# derploadxp.net
KiCad netlist of a schematic drawn in EAGLE
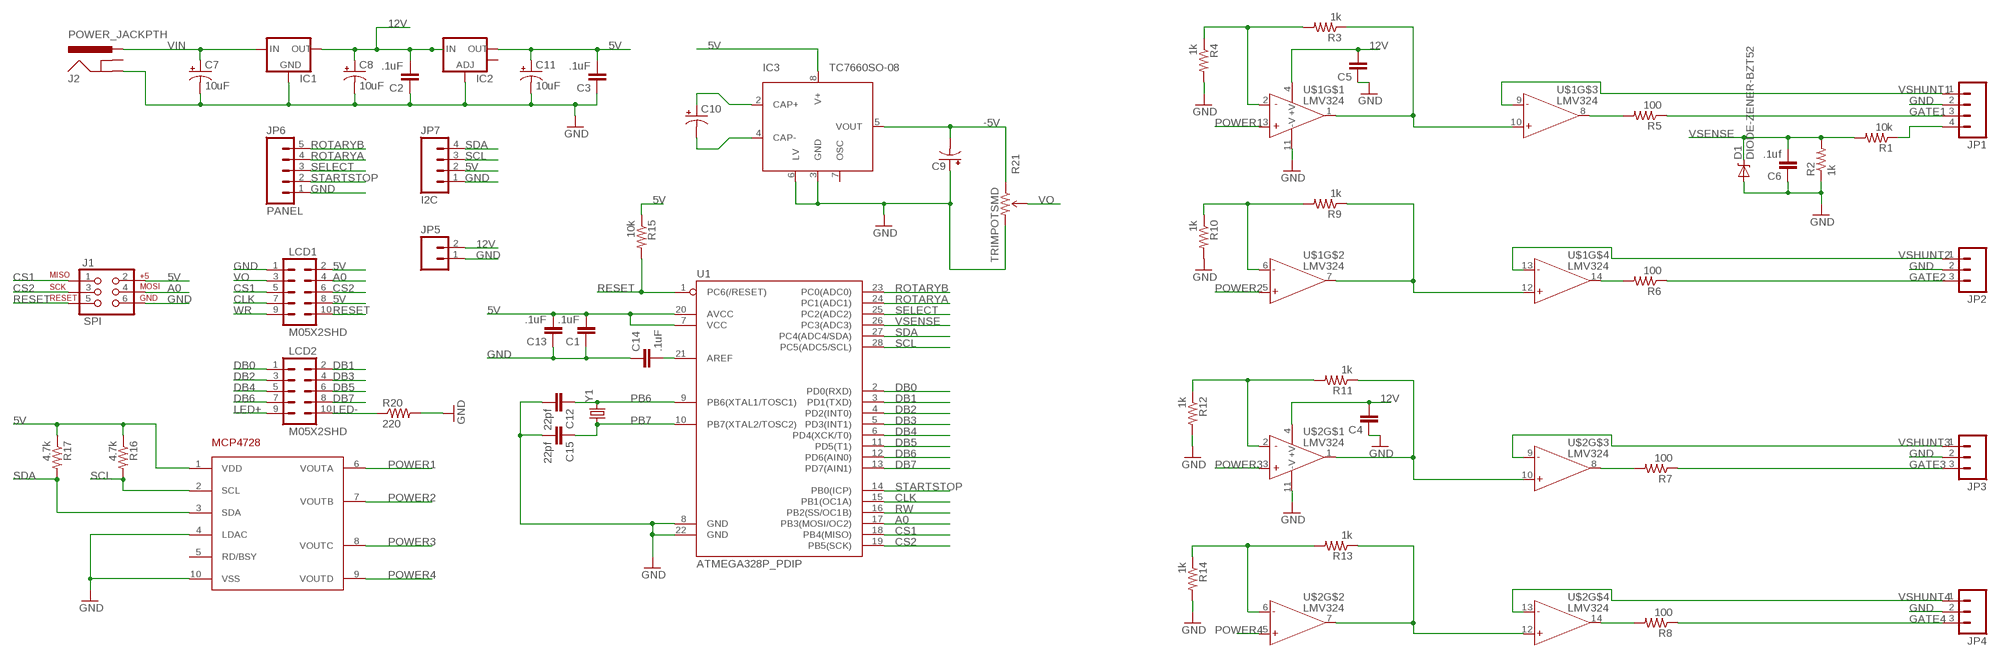
[diagram p0: schematic, sheet 1]

(export (version "E")
  (design (tool "Eeschema 10.0.6"))
  (components
    (comp (ref "C1")
      (value ".1uF")
      (footprint "eagle-import:0805")
      (libsource (lib "eagle-import") (part "CAP0805"))
    )
    (comp (ref "C2")
      (value ".1uF")
      (footprint "eagle-import:0805")
      (libsource (lib "eagle-import") (part "CAP0805"))
    )
    (comp (ref "C3")
      (value ".1uF")
      (footprint "eagle-import:0805")
      (libsource (lib "eagle-import") (part "CAP0805"))
    )
    (comp (ref "C4")
      (value "CAP0805")
      (footprint "eagle-import:0805")
      (libsource (lib "eagle-import") (part "CAP0805"))
    )
    (comp (ref "C5")
      (value "CAP0805")
      (footprint "eagle-import:0805")
      (libsource (lib "eagle-import") (part "CAP0805"))
    )
    (comp (ref "C6")
      (value ".1uf")
      (footprint "eagle-import:0805")
      (libsource (lib "eagle-import") (part "CAP0805"))
    )
    (comp (ref "C7")
      (value "10uF")
      (footprint "eagle-import:PANASONIC_C")
      (libsource (lib "eagle-import") (part "CAP_POLC"))
    )
    (comp (ref "C8")
      (value "10uF")
      (footprint "eagle-import:PANASONIC_C")
      (libsource (lib "eagle-import") (part "CAP_POLC"))
    )
    (comp (ref "C9")
      (value "CAP_POLC")
      (footprint "eagle-import:PANASONIC_C")
      (libsource (lib "eagle-import") (part "CAP_POLC"))
    )
    (comp (ref "C10")
      (value "CAP_POLC")
      (footprint "eagle-import:PANASONIC_C")
      (libsource (lib "eagle-import") (part "CAP_POLC"))
    )
    (comp (ref "C11")
      (value "10uF")
      (footprint "eagle-import:PANASONIC_C")
      (libsource (lib "eagle-import") (part "CAP_POLC"))
    )
    (comp (ref "C12")
      (value "22pf")
      (footprint "eagle-import:0805")
      (libsource (lib "eagle-import") (part "CAP0805"))
    )
    (comp (ref "C13")
      (value ".1uF")
      (footprint "eagle-import:0805")
      (libsource (lib "eagle-import") (part "CAP0805"))
    )
    (comp (ref "C14")
      (value ".1uF")
      (footprint "eagle-import:0805")
      (libsource (lib "eagle-import") (part "CAP0805"))
    )
    (comp (ref "C15")
      (value "22pf")
      (footprint "eagle-import:0805")
      (libsource (lib "eagle-import") (part "CAP0805"))
    )
    (comp (ref "D1")
      (value "DIODE-ZENER-BZT52")
      (footprint "eagle-import:SOD-323")
      (libsource (lib "eagle-import") (part "DIODE-ZENER-BZT52"))
    )
    (comp (ref "IC1")
      (value "V_REG_78XXSINK")
      (footprint "eagle-import:TO220-IGO")
      (libsource (lib "eagle-import") (part "V_REG_78XXSINK"))
    )
    (comp (ref "IC2")
      (value "V_REG_LM1117SOT223")
      (footprint "eagle-import:SOT223")
      (libsource (lib "eagle-import") (part "V_REG_LM1117SOT223"))
    )
    (comp (ref "IC3")
      (value "TC7660SO-08")
      (footprint "eagle-import:SO-08")
      (libsource (lib "eagle-import") (part "TC7660SO-08"))
    )
    (comp (ref "J1")
      (value "SPI")
      (footprint "eagle-import:2X3-NS")
      (libsource (lib "eagle-import") (part "AVR_SPI_PRG_6NS"))
    )
    (comp (ref "J2")
      (value "POWER_JACKPTH")
      (footprint "eagle-import:POWER_JACK_PTH")
      (libsource (lib "eagle-import") (part "POWER_JACKPTH"))
    )
    (comp (ref "JP1")
      (value "M04LOCK")
      (footprint "eagle-import:1X04_LOCK")
      (libsource (lib "eagle-import") (part "M04LOCK"))
    )
    (comp (ref "JP2")
      (value "M03LOCK")
      (footprint "eagle-import:1X03_LOCK")
      (libsource (lib "eagle-import") (part "M03LOCK"))
    )
    (comp (ref "JP3")
      (value "M03LOCK")
      (footprint "eagle-import:1X03_LOCK")
      (libsource (lib "eagle-import") (part "M03LOCK"))
    )
    (comp (ref "JP4")
      (value "M03LOCK")
      (footprint "eagle-import:1X03_LOCK")
      (libsource (lib "eagle-import") (part "M03LOCK"))
    )
    (comp (ref "JP5")
      (value "M02LOCK")
      (footprint "eagle-import:1X02_LOCK")
      (libsource (lib "eagle-import") (part "M02LOCK"))
    )
    (comp (ref "JP6")
      (value "PANEL")
      (footprint "eagle-import:1X05_LOCK")
      (libsource (lib "eagle-import") (part "M05LOCK"))
    )
    (comp (ref "JP7")
      (value "I2C")
      (footprint "eagle-import:1X04_LOCK")
      (libsource (lib "eagle-import") (part "M04LOCK"))
    )
    (comp (ref "LCD1")
      (value "M05X2SHD")
      (footprint "eagle-import:2X5-SHROUDED")
      (libsource (lib "eagle-import") (part "M05X2SHD"))
    )
    (comp (ref "LCD2")
      (value "M05X2SHD")
      (footprint "eagle-import:2X5-SHROUDED")
      (libsource (lib "eagle-import") (part "M05X2SHD"))
    )
    (comp (ref "R1")
      (value "10k")
      (footprint "eagle-import:0805")
      (libsource (lib "eagle-import") (part "RESISTOR0805-RES"))
    )
    (comp (ref "R2")
      (value "1k")
      (footprint "eagle-import:0805")
      (libsource (lib "eagle-import") (part "RESISTOR0805-RES"))
    )
    (comp (ref "R3")
      (value "1k")
      (footprint "eagle-import:0805")
      (libsource (lib "eagle-import") (part "RESISTOR0805-RES"))
    )
    (comp (ref "R4")
      (value "1k")
      (footprint "eagle-import:0805")
      (libsource (lib "eagle-import") (part "RESISTOR0805-RES"))
    )
    (comp (ref "R5")
      (value "100")
      (footprint "eagle-import:0805")
      (libsource (lib "eagle-import") (part "RESISTOR0805-RES"))
    )
    (comp (ref "R6")
      (value "100")
      (footprint "eagle-import:0805")
      (libsource (lib "eagle-import") (part "RESISTOR0805-RES"))
    )
    (comp (ref "R7")
      (value "100")
      (footprint "eagle-import:0805")
      (libsource (lib "eagle-import") (part "RESISTOR0805-RES"))
    )
    (comp (ref "R8")
      (value "100")
      (footprint "eagle-import:0805")
      (libsource (lib "eagle-import") (part "RESISTOR0805-RES"))
    )
    (comp (ref "R9")
      (value "1k")
      (footprint "eagle-import:0805")
      (libsource (lib "eagle-import") (part "RESISTOR0805-RES"))
    )
    (comp (ref "R10")
      (value "1k")
      (footprint "eagle-import:0805")
      (libsource (lib "eagle-import") (part "RESISTOR0805-RES"))
    )
    (comp (ref "R11")
      (value "1k")
      (footprint "eagle-import:0805")
      (libsource (lib "eagle-import") (part "RESISTOR0805-RES"))
    )
    (comp (ref "R12")
      (value "1k")
      (footprint "eagle-import:0805")
      (libsource (lib "eagle-import") (part "RESISTOR0805-RES"))
    )
    (comp (ref "R13")
      (value "1k")
      (footprint "eagle-import:0805")
      (libsource (lib "eagle-import") (part "RESISTOR0805-RES"))
    )
    (comp (ref "R14")
      (value "1k")
      (footprint "eagle-import:0805")
      (libsource (lib "eagle-import") (part "RESISTOR0805-RES"))
    )
    (comp (ref "R15")
      (value "10k")
      (footprint "eagle-import:0805")
      (libsource (lib "eagle-import") (part "RESISTOR0805-RES"))
    )
    (comp (ref "R16")
      (value "4.7k")
      (footprint "eagle-import:0805")
      (libsource (lib "eagle-import") (part "RESISTOR0805-RES"))
    )
    (comp (ref "R17")
      (value "4.7k")
      (footprint "eagle-import:0805")
      (libsource (lib "eagle-import") (part "RESISTOR0805-RES"))
    )
    (comp (ref "R20")
      (value "220")
      (footprint "eagle-import:0805")
      (libsource (lib "eagle-import") (part "RESISTOR0805-RES"))
    )
    (comp (ref "R21")
      (value "TRIMPOTSMD")
      (footprint "eagle-import:TRIMPOT-3MM")
      (libsource (lib "eagle-import") (part "TRIMPOTSMD"))
    )
    (comp (ref "U$1")
      (value "LMV324")
      (footprint "eagle-import:SO014")
      (libsource (lib "eagle-import") (part "LMV324"))
    )
    (comp (ref "U$2")
      (value "LMV324")
      (footprint "eagle-import:SO014")
      (libsource (lib "eagle-import") (part "LMV324"))
    )
    (comp (ref "U$4")
      (value "MCP4728")
      (footprint "eagle-import:MSOP10")
      (libsource (lib "eagle-import") (part "MCP4728"))
    )
    (comp (ref "U1")
      (value "ATMEGA328P_PDIP")
      (footprint "eagle-import:DIL28-3")
      (libsource (lib "eagle-import") (part "ATMEGA328P_PDIP"))
    )
    (comp (ref "Y1")
      (value "CRYSTALSMD")
      (footprint "eagle-import:HC49UP")
      (libsource (lib "eagle-import") (part "CRYSTALSMD"))
    )
  )
  (nets
    (net (code "1") (name "/-5V") (class "Default")
      (node (ref "C9") (pin "-") (pinfunction "-_-") (pintype "passive"))
      (node (ref "IC3") (pin "5") (pinfunction "VOUT_5") (pintype "bidirectional"))
      (node (ref "R21") (pin "1") (pinfunction "CCW_1") (pintype "passive"))
    )
    (net (code "2") (name "/5V") (class "Default")
      (node (ref "C1") (pin "2") (pinfunction "2_2") (pintype "passive"))
      (node (ref "C11") (pin "+") (pinfunction "+_+") (pintype "passive"))
      (node (ref "C13") (pin "2") (pinfunction "2_2") (pintype "passive"))
      (node (ref "C3") (pin "2") (pinfunction "2_2") (pintype "passive"))
      (node (ref "IC2") (pin "2") (pinfunction "OUT_2") (pintype "output"))
      (node (ref "IC3") (pin "8") (pinfunction "V+_8") (pintype "bidirectional"))
      (node (ref "J1") (pin "2") (pinfunction "2_2") (pintype "passive"))
      (node (ref "JP7") (pin "2") (pinfunction "2_2") (pintype "passive"))
      (node (ref "LCD1") (pin "2") (pinfunction "2_2") (pintype "passive"))
      (node (ref "LCD1") (pin "8") (pinfunction "8_8") (pintype "passive"))
      (node (ref "R15") (pin "1") (pinfunction "1_1") (pintype "passive"))
      (node (ref "R16") (pin "1") (pinfunction "1_1") (pintype "passive"))
      (node (ref "R17") (pin "1") (pinfunction "1_1") (pintype "passive"))
      (node (ref "U$4") (pin "1") (pinfunction "VDD_1") (pintype "bidirectional"))
      (node (ref "U1") (pin "20") (pinfunction "AVCC_20") (pintype "bidirectional"))
      (node (ref "U1") (pin "7") (pinfunction "VCC_7") (pintype "bidirectional"))
    )
    (net (code "3") (name "/12V") (class "Default")
      (node (ref "C2") (pin "2") (pinfunction "2_2") (pintype "passive"))
      (node (ref "C4") (pin "2") (pinfunction "2_2") (pintype "passive"))
      (node (ref "C5") (pin "2") (pinfunction "2_2") (pintype "passive"))
      (node (ref "C8") (pin "+") (pinfunction "+_+") (pintype "passive"))
      (node (ref "IC1") (pin "OUT") (pinfunction "OUT_OUT") (pintype "output"))
      (node (ref "IC2") (pin "3") (pinfunction "IN_3") (pintype "input"))
      (node (ref "JP5") (pin "2") (pinfunction "2_2") (pintype "passive"))
      (node (ref "U$1") (pin "4") (pinfunction "+V_4") (pintype "power_in"))
      (node (ref "U$2") (pin "4") (pinfunction "+V_4") (pintype "power_in"))
    )
    (net (code "4") (name "/A0") (class "Default")
      (node (ref "J1") (pin "4") (pinfunction "4_4") (pintype "passive"))
      (node (ref "LCD1") (pin "4") (pinfunction "4_4") (pintype "passive"))
      (node (ref "U1") (pin "17") (pinfunction "PB3(MOSI/OC2)_17") (pintype "bidirectional"))
    )
    (net (code "5") (name "/CLK") (class "Default")
      (node (ref "LCD1") (pin "7") (pinfunction "7_7") (pintype "passive"))
      (node (ref "U1") (pin "15") (pinfunction "PB1(OC1A)_15") (pintype "bidirectional"))
    )
    (net (code "6") (name "/CS1") (class "Default")
      (node (ref "J1") (pin "1") (pinfunction "1_1") (pintype "passive"))
      (node (ref "LCD1") (pin "5") (pinfunction "5_5") (pintype "passive"))
      (node (ref "U1") (pin "18") (pinfunction "PB4(MISO)_18") (pintype "bidirectional"))
    )
    (net (code "7") (name "/CS2") (class "Default")
      (node (ref "J1") (pin "3") (pinfunction "3_3") (pintype "passive"))
      (node (ref "LCD1") (pin "6") (pinfunction "6_6") (pintype "passive"))
      (node (ref "U1") (pin "19") (pinfunction "PB5(SCK)_19") (pintype "bidirectional"))
    )
    (net (code "8") (name "/DB0") (class "Default")
      (node (ref "LCD2") (pin "1") (pinfunction "1_1") (pintype "passive"))
      (node (ref "U1") (pin "2") (pinfunction "PD0(RXD)_2") (pintype "bidirectional"))
    )
    (net (code "9") (name "/DB1") (class "Default")
      (node (ref "LCD2") (pin "2") (pinfunction "2_2") (pintype "passive"))
      (node (ref "U1") (pin "3") (pinfunction "PD1(TXD)_3") (pintype "bidirectional"))
    )
    (net (code "10") (name "/DB2") (class "Default")
      (node (ref "LCD2") (pin "3") (pinfunction "3_3") (pintype "passive"))
      (node (ref "U1") (pin "4") (pinfunction "PD2(INT0)_4") (pintype "bidirectional"))
    )
    (net (code "11") (name "/DB3") (class "Default")
      (node (ref "LCD2") (pin "4") (pinfunction "4_4") (pintype "passive"))
      (node (ref "U1") (pin "5") (pinfunction "PD3(INT1)_5") (pintype "bidirectional"))
    )
    (net (code "12") (name "/DB4") (class "Default")
      (node (ref "LCD2") (pin "5") (pinfunction "5_5") (pintype "passive"))
      (node (ref "U1") (pin "6") (pinfunction "PD4(XCK/T0)_6") (pintype "bidirectional"))
    )
    (net (code "13") (name "/DB5") (class "Default")
      (node (ref "LCD2") (pin "6") (pinfunction "6_6") (pintype "passive"))
      (node (ref "U1") (pin "11") (pinfunction "PD5(T1)_11") (pintype "bidirectional"))
    )
    (net (code "14") (name "/DB6") (class "Default")
      (node (ref "LCD2") (pin "7") (pinfunction "7_7") (pintype "passive"))
      (node (ref "U1") (pin "12") (pinfunction "PD6(AIN0)_12") (pintype "bidirectional"))
    )
    (net (code "15") (name "/DB7") (class "Default")
      (node (ref "LCD2") (pin "8") (pinfunction "8_8") (pintype "passive"))
      (node (ref "U1") (pin "13") (pinfunction "PD7(AIN1)_13") (pintype "bidirectional"))
    )
    (net (code "16") (name "/GATE1") (class "Default")
      (node (ref "JP1") (pin "3") (pinfunction "3_3") (pintype "passive"))
      (node (ref "R5") (pin "1") (pinfunction "1_1") (pintype "passive"))
    )
    (net (code "17") (name "/GATE2") (class "Default")
      (node (ref "JP2") (pin "3") (pinfunction "3_3") (pintype "passive"))
      (node (ref "R6") (pin "1") (pinfunction "1_1") (pintype "passive"))
    )
    (net (code "18") (name "/GATE3") (class "Default")
      (node (ref "JP3") (pin "3") (pinfunction "3_3") (pintype "passive"))
      (node (ref "R7") (pin "1") (pinfunction "1_1") (pintype "passive"))
    )
    (net (code "19") (name "/GATE4") (class "Default")
      (node (ref "JP4") (pin "3") (pinfunction "3_3") (pintype "passive"))
      (node (ref "R8") (pin "1") (pinfunction "1_1") (pintype "passive"))
    )
    (net (code "20") (name "/LED+") (class "Default")
      (node (ref "LCD2") (pin "9") (pinfunction "9_9") (pintype "passive"))
    )
    (net (code "21") (name "/LED-") (class "Default")
      (node (ref "LCD2") (pin "10") (pinfunction "10_10") (pintype "passive"))
      (node (ref "R20") (pin "1") (pinfunction "1_1") (pintype "passive"))
    )
    (net (code "22") (name "/PB6") (class "Default")
      (node (ref "C12") (pin "1") (pinfunction "1_1") (pintype "passive"))
      (node (ref "U1") (pin "9") (pinfunction "PB6(XTAL1/TOSC1)_9") (pintype "bidirectional"))
      (node (ref "Y1") (pin "2") (pinfunction "2_2") (pintype "passive"))
    )
    (net (code "23") (name "/PB7") (class "Default")
      (node (ref "C15") (pin "1") (pinfunction "1_1") (pintype "passive"))
      (node (ref "U1") (pin "10") (pinfunction "PB7(XTAL2/TOSC2)_10") (pintype "bidirectional"))
      (node (ref "Y1") (pin "1") (pinfunction "1_1") (pintype "passive"))
    )
    (net (code "24") (name "/POWER1") (class "Default")
      (node (ref "U$1") (pin "3") (pinfunction "+IN_3") (pintype "input"))
      (node (ref "U$4") (pin "6") (pinfunction "VOUTA_6") (pintype "bidirectional"))
    )
    (net (code "25") (name "/POWER2") (class "Default")
      (node (ref "U$1") (pin "5") (pinfunction "+IN_5") (pintype "power_in"))
      (node (ref "U$4") (pin "7") (pinfunction "VOUTB_7") (pintype "bidirectional"))
    )
    (net (code "26") (name "/POWER3") (class "Default")
      (node (ref "U$2") (pin "3") (pinfunction "+IN_3") (pintype "input"))
      (node (ref "U$4") (pin "8") (pinfunction "VOUTC_8") (pintype "bidirectional"))
    )
    (net (code "27") (name "/POWER4") (class "Default")
      (node (ref "U$2") (pin "5") (pinfunction "+IN_5") (pintype "power_in"))
      (node (ref "U$4") (pin "9") (pinfunction "VOUTD_9") (pintype "bidirectional"))
    )
    (net (code "28") (name "/RESET") (class "Default")
      (node (ref "J1") (pin "5") (pinfunction "5_5") (pintype "passive"))
      (node (ref "LCD1") (pin "10") (pinfunction "10_10") (pintype "passive"))
      (node (ref "R15") (pin "2") (pinfunction "2_2") (pintype "passive"))
      (node (ref "U1") (pin "1") (pinfunction "PC6(/RESET)_1") (pintype "bidirectional"))
    )
    (net (code "29") (name "/ROTARYA") (class "Default")
      (node (ref "JP6") (pin "4") (pinfunction "4_4") (pintype "passive"))
      (node (ref "U1") (pin "24") (pinfunction "PC1(ADC1)_24") (pintype "bidirectional"))
    )
    (net (code "30") (name "/ROTARYB") (class "Default")
      (node (ref "JP6") (pin "5") (pinfunction "5_5") (pintype "passive"))
      (node (ref "U1") (pin "23") (pinfunction "PC0(ADC0)_23") (pintype "bidirectional"))
    )
    (net (code "31") (name "/RW") (class "Default")
      (node (ref "U1") (pin "16") (pinfunction "PB2(SS/OC1B)_16") (pintype "bidirectional"))
    )
    (net (code "32") (name "/SCL") (class "Default")
      (node (ref "JP7") (pin "3") (pinfunction "3_3") (pintype "passive"))
      (node (ref "R16") (pin "2") (pinfunction "2_2") (pintype "passive"))
      (node (ref "U$4") (pin "2") (pinfunction "SCL_2") (pintype "bidirectional"))
      (node (ref "U1") (pin "28") (pinfunction "PC5(ADC5/SCL)_28") (pintype "bidirectional"))
    )
    (net (code "33") (name "/SDA") (class "Default")
      (node (ref "JP7") (pin "4") (pinfunction "4_4") (pintype "passive"))
      (node (ref "R17") (pin "2") (pinfunction "2_2") (pintype "passive"))
      (node (ref "U$4") (pin "3") (pinfunction "SDA_3") (pintype "bidirectional"))
      (node (ref "U1") (pin "27") (pinfunction "PC4(ADC4/SDA)_27") (pintype "bidirectional"))
    )
    (net (code "34") (name "/SELECT") (class "Default")
      (node (ref "JP6") (pin "3") (pinfunction "3_3") (pintype "passive"))
      (node (ref "U1") (pin "25") (pinfunction "PC2(ADC2)_25") (pintype "bidirectional"))
    )
    (net (code "35") (name "/STARTSTOP") (class "Default")
      (node (ref "JP6") (pin "2") (pinfunction "2_2") (pintype "passive"))
      (node (ref "U1") (pin "14") (pinfunction "PB0(ICP)_14") (pintype "bidirectional"))
    )
    (net (code "36") (name "/VIN") (class "Default")
      (node (ref "C7") (pin "+") (pinfunction "+_+") (pintype "passive"))
      (node (ref "IC1") (pin "IN") (pinfunction "IN_IN") (pintype "input"))
      (node (ref "J2") (pin "PWR") (pinfunction "PWR_PWR") (pintype "bidirectional"))
    )
    (net (code "37") (name "/VO") (class "Default")
      (node (ref "LCD1") (pin "3") (pinfunction "3_3") (pintype "passive"))
      (node (ref "R21") (pin "2") (pinfunction "WIPER_2") (pintype "passive"))
    )
    (net (code "38") (name "/VSENSE") (class "Default")
      (node (ref "C6") (pin "2") (pinfunction "2_2") (pintype "passive"))
      (node (ref "D1") (pin "1") (pinfunction "C_1") (pintype "passive"))
      (node (ref "R1") (pin "2") (pinfunction "2_2") (pintype "passive"))
      (node (ref "R2") (pin "2") (pinfunction "2_2") (pintype "passive"))
      (node (ref "U1") (pin "26") (pinfunction "PC3(ADC3)_26") (pintype "bidirectional"))
    )
    (net (code "39") (name "/VSHUNT1") (class "Default")
      (node (ref "JP1") (pin "1") (pinfunction "1_1") (pintype "passive"))
      (node (ref "U$1") (pin "9") (pinfunction "-IN_9") (pintype "power_in"))
    )
    (net (code "40") (name "/VSHUNT2") (class "Default")
      (node (ref "JP2") (pin "1") (pinfunction "1_1") (pintype "passive"))
      (node (ref "U$1") (pin "13") (pinfunction "-IN_13") (pintype "power_in"))
    )
    (net (code "41") (name "/VSHUNT3") (class "Default")
      (node (ref "JP3") (pin "1") (pinfunction "1_1") (pintype "passive"))
      (node (ref "U$2") (pin "9") (pinfunction "-IN_9") (pintype "power_in"))
    )
    (net (code "42") (name "/VSHUNT4") (class "Default")
      (node (ref "JP4") (pin "1") (pinfunction "1_1") (pintype "passive"))
      (node (ref "U$2") (pin "13") (pinfunction "-IN_13") (pintype "power_in"))
    )
    (net (code "43") (name "/WR") (class "Default")
      (node (ref "LCD1") (pin "9") (pinfunction "9_9") (pintype "passive"))
    )
    (net (code "44") (name "GND") (class "Default")
      (node (ref "C1") (pin "1") (pinfunction "1_1") (pintype "passive"))
      (node (ref "C11") (pin "-") (pinfunction "-_-") (pintype "passive"))
      (node (ref "C12") (pin "2") (pinfunction "2_2") (pintype "passive"))
      (node (ref "C13") (pin "1") (pinfunction "1_1") (pintype "passive"))
      (node (ref "C14") (pin "1") (pinfunction "1_1") (pintype "passive"))
      (node (ref "C15") (pin "2") (pinfunction "2_2") (pintype "passive"))
      (node (ref "C2") (pin "1") (pinfunction "1_1") (pintype "passive"))
      (node (ref "C3") (pin "1") (pinfunction "1_1") (pintype "passive"))
      (node (ref "C4") (pin "1") (pinfunction "1_1") (pintype "passive"))
      (node (ref "C5") (pin "1") (pinfunction "1_1") (pintype "passive"))
      (node (ref "C6") (pin "1") (pinfunction "1_1") (pintype "passive"))
      (node (ref "C7") (pin "-") (pinfunction "-_-") (pintype "passive"))
      (node (ref "C8") (pin "-") (pinfunction "-_-") (pintype "passive"))
      (node (ref "C9") (pin "+") (pinfunction "+_+") (pintype "passive"))
      (node (ref "D1") (pin "2") (pinfunction "A_2") (pintype "passive"))
      (node (ref "IC1") (pin "GND") (pinfunction "GND_GND") (pintype "input"))
      (node (ref "IC2") (pin "1") (pinfunction "ADJ_1") (pintype "input"))
      (node (ref "IC3") (pin "3") (pinfunction "GND_3") (pintype "bidirectional"))
      (node (ref "IC3") (pin "6") (pinfunction "LV_6") (pintype "bidirectional"))
      (node (ref "J1") (pin "6") (pinfunction "6_6") (pintype "passive"))
      (node (ref "J2") (pin "GND") (pinfunction "GND_GND") (pintype "bidirectional"))
      (node (ref "JP1") (pin "2") (pinfunction "2_2") (pintype "passive"))
      (node (ref "JP2") (pin "2") (pinfunction "2_2") (pintype "passive"))
      (node (ref "JP3") (pin "2") (pinfunction "2_2") (pintype "passive"))
      (node (ref "JP4") (pin "2") (pinfunction "2_2") (pintype "passive"))
      (node (ref "JP5") (pin "1") (pinfunction "1_1") (pintype "passive"))
      (node (ref "JP6") (pin "1") (pinfunction "1_1") (pintype "passive"))
      (node (ref "JP7") (pin "1") (pinfunction "1_1") (pintype "passive"))
      (node (ref "LCD1") (pin "1") (pinfunction "1_1") (pintype "passive"))
      (node (ref "R10") (pin "2") (pinfunction "2_2") (pintype "passive"))
      (node (ref "R12") (pin "2") (pinfunction "2_2") (pintype "passive"))
      (node (ref "R14") (pin "2") (pinfunction "2_2") (pintype "passive"))
      (node (ref "R2") (pin "1") (pinfunction "1_1") (pintype "passive"))
      (node (ref "R20") (pin "2") (pinfunction "2_2") (pintype "passive"))
      (node (ref "R21") (pin "3") (pinfunction "CW_3") (pintype "passive"))
      (node (ref "R4") (pin "2") (pinfunction "2_2") (pintype "passive"))
      (node (ref "U$1") (pin "11") (pinfunction "-V_11") (pintype "power_in"))
      (node (ref "U$2") (pin "11") (pinfunction "-V_11") (pintype "power_in"))
      (node (ref "U$4") (pin "10") (pinfunction "VSS_10") (pintype "bidirectional"))
      (node (ref "U$4") (pin "4") (pinfunction "LDAC_4") (pintype "bidirectional"))
      (node (ref "U1") (pin "22") (pinfunction "GND_22") (pintype "bidirectional"))
      (node (ref "U1") (pin "8") (pinfunction "GND_8") (pintype "bidirectional"))
    )
    (net (code "45") (name "Net-(IC3-CAP+)") (class "Default")
      (node (ref "C10") (pin "+") (pinfunction "+_+") (pintype "passive"))
      (node (ref "IC3") (pin "2") (pinfunction "CAP+_2") (pintype "bidirectional"))
    )
    (net (code "46") (name "Net-(IC3-CAP-)") (class "Default")
      (node (ref "C10") (pin "-") (pinfunction "-_-") (pintype "passive"))
      (node (ref "IC3") (pin "4") (pinfunction "CAP-_4") (pintype "bidirectional"))
    )
    (net (code "47") (name "Net-(JP1-Pad4)") (class "Default")
      (node (ref "JP1") (pin "4") (pinfunction "4_4") (pintype "passive"))
      (node (ref "R1") (pin "1") (pinfunction "1_1") (pintype "passive"))
    )
    (net (code "48") (name "Net-(U$1A--IN)") (class "Default")
      (node (ref "R3") (pin "2") (pinfunction "2_2") (pintype "passive"))
      (node (ref "R4") (pin "1") (pinfunction "1_1") (pintype "passive"))
      (node (ref "U$1") (pin "2") (pinfunction "-IN_2") (pintype "input"))
    )
    (net (code "49") (name "Net-(U$1A-OUT)") (class "Default")
      (node (ref "R3") (pin "1") (pinfunction "1_1") (pintype "passive"))
      (node (ref "U$1") (pin "1") (pinfunction "OUT_1") (pintype "output"))
      (node (ref "U$1") (pin "10") (pinfunction "+IN_10") (pintype "power_in"))
    )
    (net (code "50") (name "Net-(U$1B--IN)") (class "Default")
      (node (ref "R10") (pin "1") (pinfunction "1_1") (pintype "passive"))
      (node (ref "R9") (pin "2") (pinfunction "2_2") (pintype "passive"))
      (node (ref "U$1") (pin "6") (pinfunction "-IN_6") (pintype "power_in"))
    )
    (net (code "51") (name "Net-(U$1B-OUT)") (class "Default")
      (node (ref "R9") (pin "1") (pinfunction "1_1") (pintype "passive"))
      (node (ref "U$1") (pin "12") (pinfunction "+IN_12") (pintype "power_in"))
      (node (ref "U$1") (pin "7") (pinfunction "OUT_7") (pintype "power_in"))
    )
    (net (code "52") (name "Net-(U$1C-OUT)") (class "Default")
      (node (ref "R5") (pin "2") (pinfunction "2_2") (pintype "passive"))
      (node (ref "U$1") (pin "8") (pinfunction "OUT_8") (pintype "power_in"))
    )
    (net (code "53") (name "Net-(U$1D-OUT)") (class "Default")
      (node (ref "R6") (pin "2") (pinfunction "2_2") (pintype "passive"))
      (node (ref "U$1") (pin "14") (pinfunction "OUT_14") (pintype "power_in"))
    )
    (net (code "54") (name "Net-(U$2A--IN)") (class "Default")
      (node (ref "R11") (pin "2") (pinfunction "2_2") (pintype "passive"))
      (node (ref "R12") (pin "1") (pinfunction "1_1") (pintype "passive"))
      (node (ref "U$2") (pin "2") (pinfunction "-IN_2") (pintype "input"))
    )
    (net (code "55") (name "Net-(U$2A-OUT)") (class "Default")
      (node (ref "R11") (pin "1") (pinfunction "1_1") (pintype "passive"))
      (node (ref "U$2") (pin "1") (pinfunction "OUT_1") (pintype "output"))
      (node (ref "U$2") (pin "10") (pinfunction "+IN_10") (pintype "power_in"))
    )
    (net (code "56") (name "Net-(U$2B--IN)") (class "Default")
      (node (ref "R13") (pin "2") (pinfunction "2_2") (pintype "passive"))
      (node (ref "R14") (pin "1") (pinfunction "1_1") (pintype "passive"))
      (node (ref "U$2") (pin "6") (pinfunction "-IN_6") (pintype "power_in"))
    )
    (net (code "57") (name "Net-(U$2B-OUT)") (class "Default")
      (node (ref "R13") (pin "1") (pinfunction "1_1") (pintype "passive"))
      (node (ref "U$2") (pin "12") (pinfunction "+IN_12") (pintype "power_in"))
      (node (ref "U$2") (pin "7") (pinfunction "OUT_7") (pintype "power_in"))
    )
    (net (code "58") (name "Net-(U$2C-OUT)") (class "Default")
      (node (ref "R7") (pin "2") (pinfunction "2_2") (pintype "passive"))
      (node (ref "U$2") (pin "8") (pinfunction "OUT_8") (pintype "power_in"))
    )
    (net (code "59") (name "Net-(U$2D-OUT)") (class "Default")
      (node (ref "R8") (pin "2") (pinfunction "2_2") (pintype "passive"))
      (node (ref "U$2") (pin "14") (pinfunction "OUT_14") (pintype "power_in"))
    )
    (net (code "60") (name "Net-(U1-AREF)") (class "Default")
      (node (ref "C14") (pin "2") (pinfunction "2_2") (pintype "passive"))
      (node (ref "U1") (pin "21") (pinfunction "AREF_21") (pintype "bidirectional"))
    )
    (net (code "61") (name "unconnected-(IC2-OUT-Pad4)") (class "Default")
      (node (ref "IC2") (pin "4") (pinfunction "OUT_4") (pintype "output"))
    )
    (net (code "62") (name "unconnected-(IC3-OSC-Pad7)") (class "Default")
      (node (ref "IC3") (pin "7") (pinfunction "OSC_7") (pintype "bidirectional"))
    )
    (net (code "63") (name "unconnected-(J2-PadGNDBREAK)") (class "Default")
      (node (ref "J2") (pin "GNDBREAK") (pinfunction "GNDBREAK_GNDBREAK") (pintype "bidirectional"))
    )
    (net (code "64") (name "unconnected-(U$4-RD{slash}BSY-Pad5)") (class "Default")
      (node (ref "U$4") (pin "5") (pinfunction "RD/BSY_5") (pintype "bidirectional"))
    )
  )
)
